# switcher.net
KiCad netlist of a schematic drawn in Altium Designer
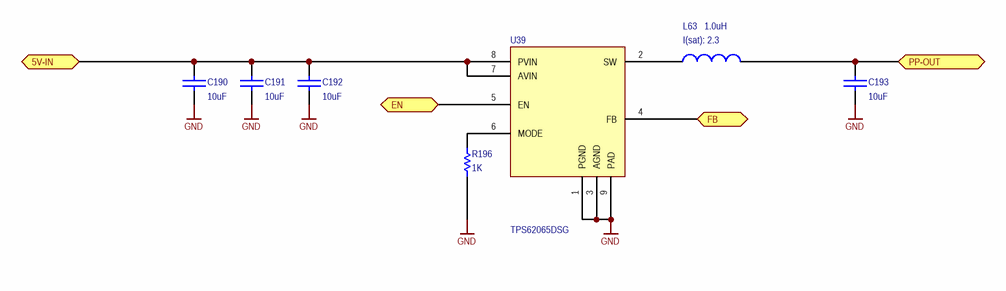
[diagram p0: switcher.SchDoc]

(export (version "E")
  (design (tool "Eeschema 10.0.6"))
  (components
    (comp (ref "C190")
      (value "10uF")
      (footprint "generic:0603")
      (description "Ceramic Capacitor 10uF ±20% 25V X5R 0603")
      (fields (field (name "MANUFACTURER") "Samsung") (field (name "VOLTAGE") "25V"))
      (libsource (lib "generic") (part "CAP 0603"))
    )
    (comp (ref "C191")
      (value "10uF")
      (footprint "generic:0603")
      (description "Ceramic Capacitor 10uF ±20% 25V X5R 0603")
      (fields (field (name "MANUFACTURER") "Samsung") (field (name "VOLTAGE") "25V"))
      (libsource (lib "generic") (part "CAP 0603"))
    )
    (comp (ref "C192")
      (value "10uF")
      (footprint "generic:0603")
      (description "Ceramic Capacitor 10uF ±20% 25V X5R 0603")
      (fields (field (name "MANUFACTURER") "Samsung") (field (name "VOLTAGE") "25V"))
      (libsource (lib "generic") (part "CAP 0603"))
    )
    (comp (ref "C193")
      (value "10uF")
      (footprint "generic:0603")
      (description "Ceramic Capacitor 10uF ±20% 25V X5R 0603")
      (fields (field (name "MANUFACTURER") "Samsung") (field (name "VOLTAGE") "25V"))
      (libsource (lib "generic") (part "CAP 0603"))
    )
    (comp (ref "L63")
      (value "1.0uH")
      (footprint "ASPI-0310FS")
      (description "Wirewound Ferite Power Inductor 1.0uH ±20% 2.3A SMD")
      (fields
        (field (name "MANUFACTURER") "Abracon")
        (field (name "I(SAT)") "2.3")
        (field (name "TOLERANCE") "±30%")
      )
      (libsource (lib "CamBoard_Pico_70.19K") (part "COIL"))
    )
    (comp (ref "R196")
      (value "1K")
      (footprint "generic:0402")
      (description "Thick Film Resistor 1k ±1% 0402")
      (fields (field (name "MANUFACTURER") "Yageo") (field (name "TOLERANCE") "±1%"))
      (libsource (lib "generic") (part "RES 0402"))
    )
    (comp (ref "U39")
      (value "TPS62065DSG")
      (footprint "DSG")
      (description "Tiny 6V input 2A Synchronous Buck w/ Internal Switch and MODE")
      (fields (field (name "MANUFACTURER") "Texas Instruments"))
      (libsource (lib "ti") (part "TPS62065"))
    )
  )
  (nets
    (net (code "1") (name "/5V-IN") (class "Default")
      (node (ref "C190") (pin "2") (pinfunction "2_2") (pintype "passive"))
      (node (ref "C191") (pin "2") (pinfunction "2_2") (pintype "passive"))
      (node (ref "C192") (pin "2") (pinfunction "2_2") (pintype "passive"))
      (node (ref "U39") (pin "7") (pinfunction "AVIN_7") (pintype "passive"))
      (node (ref "U39") (pin "8") (pinfunction "PVIN_8") (pintype "passive"))
    )
    (net (code "2") (name "/EN") (class "Default")
      (node (ref "U39") (pin "5") (pinfunction "EN_5") (pintype "passive"))
    )
    (net (code "3") (name "/FB") (class "Default")
      (node (ref "U39") (pin "4") (pinfunction "FB_4") (pintype "passive"))
    )
    (net (code "4") (name "/PP-OUT") (class "Default")
      (node (ref "C193") (pin "2") (pinfunction "2_2") (pintype "passive"))
      (node (ref "L63") (pin "2") (pinfunction "2_2") (pintype "passive"))
    )
    (net (code "5") (name "GND") (class "Default")
      (node (ref "C190") (pin "1") (pinfunction "1_1") (pintype "passive"))
      (node (ref "C191") (pin "1") (pinfunction "1_1") (pintype "passive"))
      (node (ref "C192") (pin "1") (pinfunction "1_1") (pintype "passive"))
      (node (ref "C193") (pin "1") (pinfunction "1_1") (pintype "passive"))
      (node (ref "R196") (pin "1") (pinfunction "1_1") (pintype "passive"))
      (node (ref "U39") (pin "1") (pinfunction "PGND_1") (pintype "passive"))
      (node (ref "U39") (pin "3") (pinfunction "AGND_3") (pintype "passive"))
      (node (ref "U39") (pin "9") (pinfunction "PAD_9") (pintype "passive"))
    )
    (net (code "6") (name "Net-(U39-MODE)") (class "Default")
      (node (ref "R196") (pin "2") (pinfunction "2_2") (pintype "passive"))
      (node (ref "U39") (pin "6") (pinfunction "MODE_6") (pintype "passive"))
    )
    (net (code "7") (name "Net-(U39-SW)") (class "Default")
      (node (ref "L63") (pin "1") (pinfunction "1_1") (pintype "passive"))
      (node (ref "U39") (pin "2") (pinfunction "SW_2") (pintype "passive"))
    )
  )
)
